# power_distribution.net
KiCad netlist of a schematic drawn in EAGLE
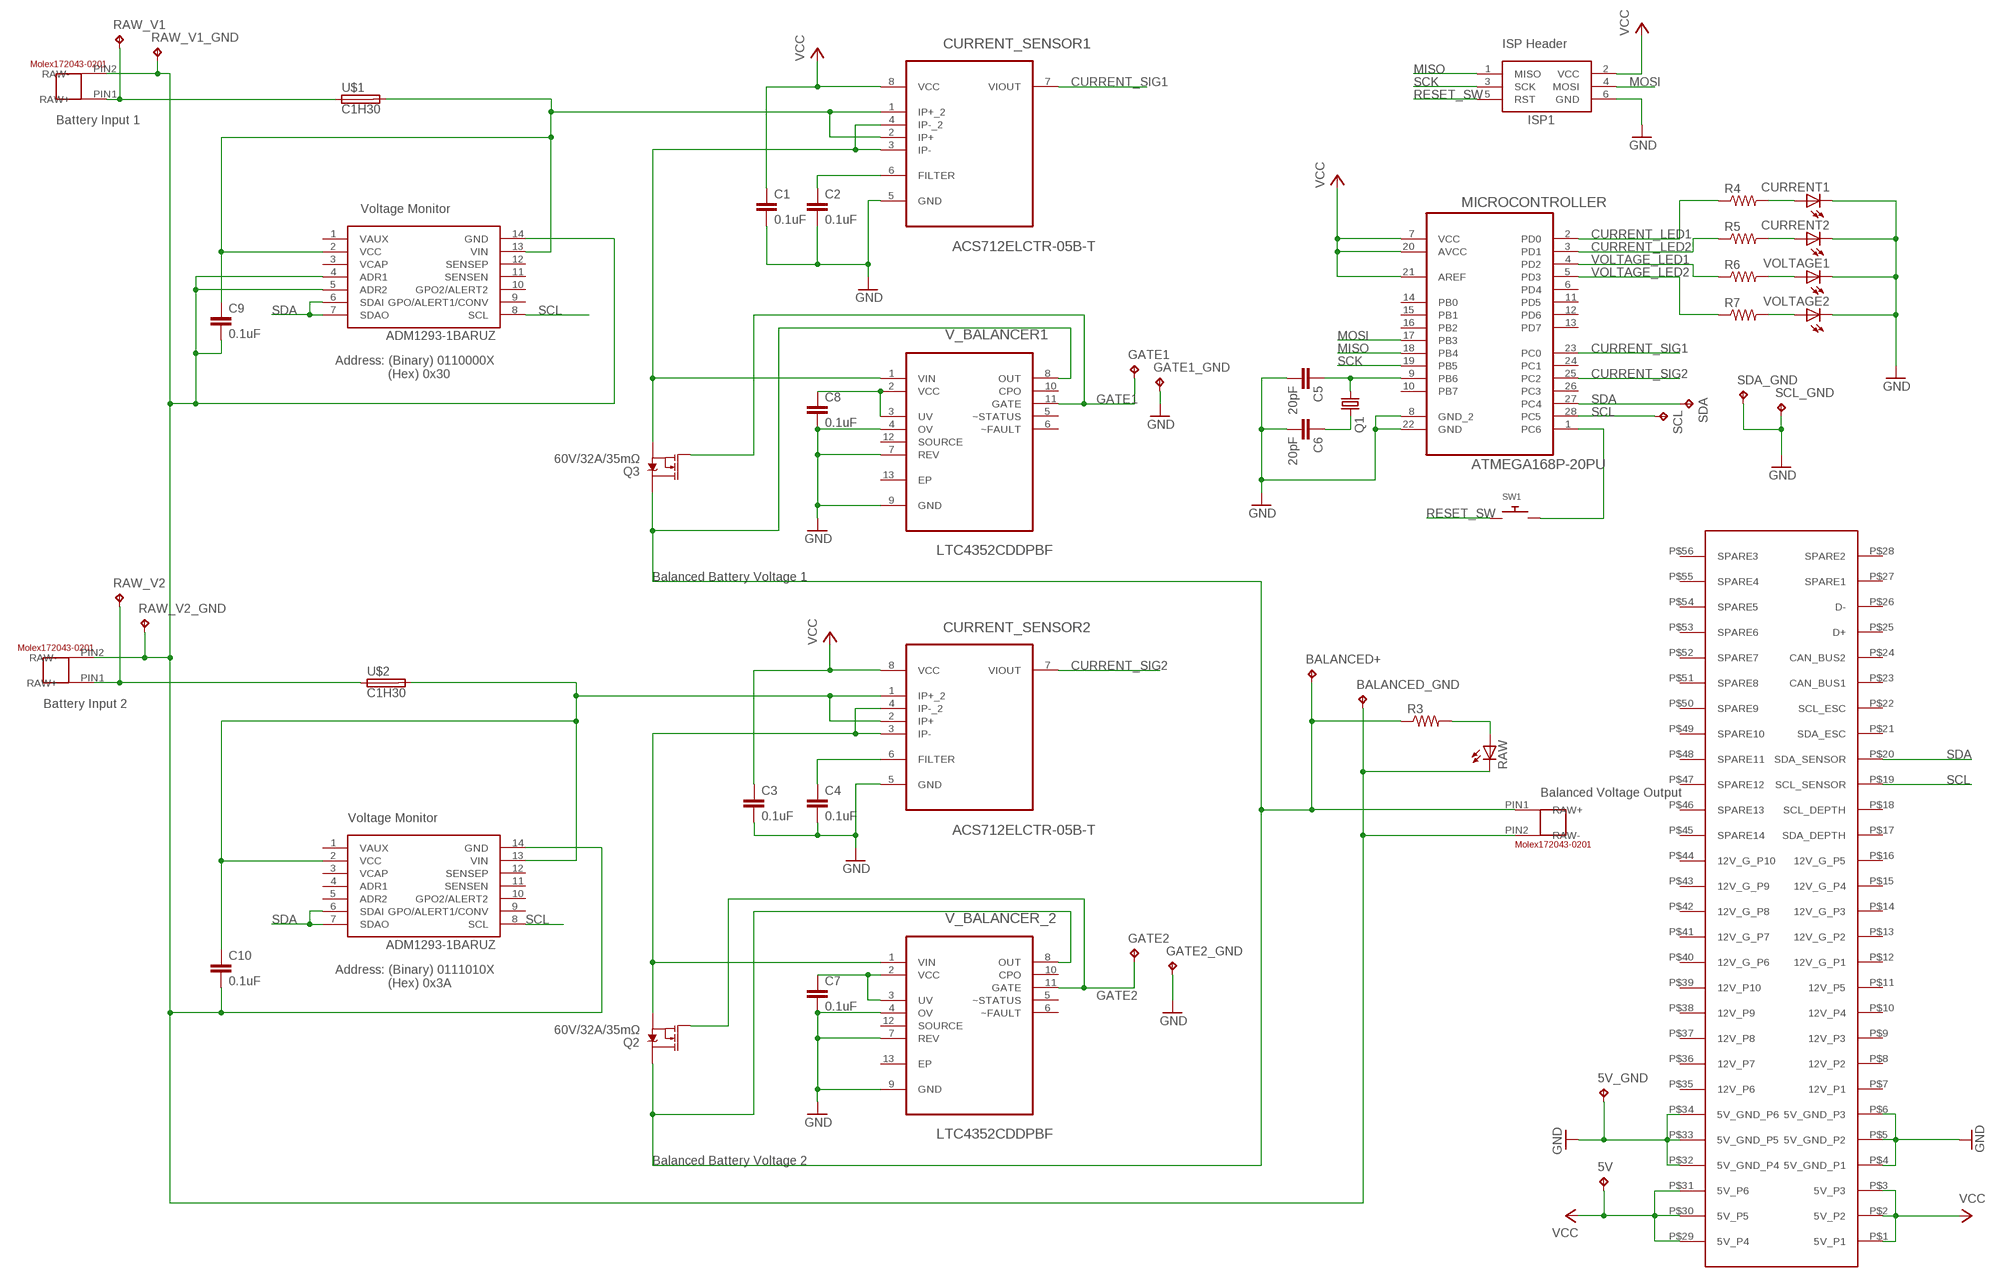
[diagram p0: schematic, sheet 1]

(export (version "E")
  (design (tool "Eeschema 10.0.6"))
  (components
    (comp (ref "5V")
      (value "TPPAD1-13")
      (footprint "eagle-import:P1-13")
      (libsource (lib "eagle-import") (part "TPPAD1-13"))
    )
    (comp (ref "5V_GND")
      (value "TPPAD1-13")
      (footprint "eagle-import:P1-13")
      (libsource (lib "eagle-import") (part "TPPAD1-13"))
    )
    (comp (ref "BALANCED+")
      (value "TPPAD1-13")
      (footprint "eagle-import:P1-13")
      (libsource (lib "eagle-import") (part "TPPAD1-13"))
    )
    (comp (ref "BALANCED_GND")
      (value "TPPAD1-13")
      (footprint "eagle-import:P1-13")
      (libsource (lib "eagle-import") (part "TPPAD1-13"))
    )
    (comp (ref "C1")
      (value "0.1uF")
      (footprint "eagle-import:CAP-PTH-SMALL-KIT")
      (libsource (lib "eagle-import") (part "0.1UF-KIT-EZ-50V-20%"))
    )
    (comp (ref "C2")
      (value "0.1uF")
      (footprint "eagle-import:CAP-PTH-SMALL-KIT")
      (libsource (lib "eagle-import") (part "0.1UF-KIT-EZ-50V-20%"))
    )
    (comp (ref "C3")
      (value "0.1uF")
      (footprint "eagle-import:CAP-PTH-SMALL-KIT")
      (libsource (lib "eagle-import") (part "0.1UF-KIT-EZ-50V-20%"))
    )
    (comp (ref "C4")
      (value "0.1uF")
      (footprint "eagle-import:CAP-PTH-SMALL-KIT")
      (libsource (lib "eagle-import") (part "0.1UF-KIT-EZ-50V-20%"))
    )
    (comp (ref "C5")
      (value "20pF")
      (footprint "eagle-import:CAP-PTH-SMALL-KIT")
      (libsource (lib "eagle-import") (part "0.1UF-KIT-EZ-50V-20%"))
    )
    (comp (ref "C6")
      (value "20pF")
      (footprint "eagle-import:CAP-PTH-SMALL-KIT")
      (libsource (lib "eagle-import") (part "0.1UF-KIT-EZ-50V-20%"))
    )
    (comp (ref "C7")
      (value "0.1uF")
      (footprint "eagle-import:CAP-PTH-SMALL-KIT")
      (libsource (lib "eagle-import") (part "0.1UF-KIT-EZ-50V-20%"))
    )
    (comp (ref "C8")
      (value "0.1uF")
      (footprint "eagle-import:CAP-PTH-SMALL-KIT")
      (libsource (lib "eagle-import") (part "0.1UF-KIT-EZ-50V-20%"))
    )
    (comp (ref "C9")
      (value "0.1uF")
      (footprint "eagle-import:CAP-PTH-SMALL-KIT")
      (libsource (lib "eagle-import") (part "0.1UF-KIT-EZ-50V-20%"))
    )
    (comp (ref "C10")
      (value "0.1uF")
      (footprint "eagle-import:CAP-PTH-SMALL-KIT")
      (libsource (lib "eagle-import") (part "0.1UF-KIT-EZ-50V-20%"))
    )
    (comp (ref "CURRENT1")
      (value "LED3MM")
      (footprint "eagle-import:LED3MM")
      (libsource (lib "eagle-import") (part "LED3MM"))
    )
    (comp (ref "CURRENT2")
      (value "LED3MM")
      (footprint "eagle-import:LED3MM")
      (libsource (lib "eagle-import") (part "LED3MM"))
    )
    (comp (ref "CURRENT_SENSOR1")
      (value "ACS712ELCTR-05B-T")
      (footprint "eagle-import:SOIC127P600X175-8N")
      (libsource (lib "eagle-import") (part "ACS712ELCTR-05B-T"))
    )
    (comp (ref "CURRENT_SENSOR2")
      (value "ACS712ELCTR-05B-T")
      (footprint "eagle-import:SOIC127P600X175-8N")
      (libsource (lib "eagle-import") (part "ACS712ELCTR-05B-T"))
    )
    (comp (ref "GATE1")
      (value "TPPAD1-13")
      (footprint "eagle-import:P1-13")
      (libsource (lib "eagle-import") (part "TPPAD1-13"))
    )
    (comp (ref "GATE1_GND")
      (value "TPPAD1-13")
      (footprint "eagle-import:P1-13")
      (libsource (lib "eagle-import") (part "TPPAD1-13"))
    )
    (comp (ref "GATE2")
      (value "TPPAD1-13")
      (footprint "eagle-import:P1-13")
      (libsource (lib "eagle-import") (part "TPPAD1-13"))
    )
    (comp (ref "GATE2_GND")
      (value "TPPAD1-13")
      (footprint "eagle-import:P1-13")
      (libsource (lib "eagle-import") (part "TPPAD1-13"))
    )
    (comp (ref "INPUT1")
      (value "MOLEX172043-0201")
      (footprint "eagle-import:MOLEX172043-0201")
      (libsource (lib "eagle-import") (part "MOLEX172043-0201"))
    )
    (comp (ref "INPUT2")
      (value "MOLEX172043-0201")
      (footprint "eagle-import:MOLEX172043-0201")
      (libsource (lib "eagle-import") (part "MOLEX172043-0201"))
    )
    (comp (ref "ISP1")
      (value "AVRISP-6")
      (footprint "eagle-import:AVRISP")
      (libsource (lib "eagle-import") (part "AVRISP-6"))
    )
    (comp (ref "MICROCONTROLLER")
      (value "ATMEGA168P-20PU")
      (footprint "eagle-import:DIP254P762X457-28")
      (libsource (lib "eagle-import") (part "ATMEGA168P-20PU"))
    )
    (comp (ref "OUTPUT")
      (value "MOLEX172043-0201")
      (footprint "eagle-import:MOLEX172043-0201")
      (libsource (lib "eagle-import") (part "MOLEX172043-0201"))
    )
    (comp (ref "Q1")
      (value "CRYSTALHC49U-V")
      (footprint "eagle-import:HC49U-V")
      (libsource (lib "eagle-import") (part "CRYSTALHC49U-V"))
    )
    (comp (ref "Q2")
      (value "60V/32A/35mΩ")
      (footprint "eagle-import:TO220V")
      (libsource (lib "eagle-import") (part "MOSFET-NCH-FQP30N06L"))
    )
    (comp (ref "Q3")
      (value "60V/32A/35mΩ")
      (footprint "eagle-import:TO220V")
      (libsource (lib "eagle-import") (part "MOSFET-NCH-FQP30N06L"))
    )
    (comp (ref "R3")
      (value "R-US_0207/12")
      (footprint "eagle-import:0207_12")
      (libsource (lib "eagle-import") (part "R-US_0207/12"))
    )
    (comp (ref "R4")
      (value "R-US_0207/12")
      (footprint "eagle-import:0207_12")
      (libsource (lib "eagle-import") (part "R-US_0207/12"))
    )
    (comp (ref "R5")
      (value "R-US_0207/12")
      (footprint "eagle-import:0207_12")
      (libsource (lib "eagle-import") (part "R-US_0207/12"))
    )
    (comp (ref "R6")
      (value "R-US_0207/12")
      (footprint "eagle-import:0207_12")
      (libsource (lib "eagle-import") (part "R-US_0207/12"))
    )
    (comp (ref "R7")
      (value "R-US_0207/12")
      (footprint "eagle-import:0207_12")
      (libsource (lib "eagle-import") (part "R-US_0207/12"))
    )
    (comp (ref "RAW")
      (value "LED3MM")
      (footprint "eagle-import:LED3MM")
      (libsource (lib "eagle-import") (part "LED3MM"))
    )
    (comp (ref "RAW_V1")
      (value "TPPAD1-13")
      (footprint "eagle-import:P1-13")
      (libsource (lib "eagle-import") (part "TPPAD1-13"))
    )
    (comp (ref "RAW_V1_GND")
      (value "TPPAD1-13")
      (footprint "eagle-import:P1-13")
      (libsource (lib "eagle-import") (part "TPPAD1-13"))
    )
    (comp (ref "RAW_V2")
      (value "TPPAD1-13")
      (footprint "eagle-import:P1-13")
      (libsource (lib "eagle-import") (part "TPPAD1-13"))
    )
    (comp (ref "RAW_V2_GND")
      (value "TPPAD1-13")
      (footprint "eagle-import:P1-13")
      (libsource (lib "eagle-import") (part "TPPAD1-13"))
    )
    (comp (ref "SCL")
      (value "TPPAD1-13")
      (footprint "eagle-import:P1-13")
      (libsource (lib "eagle-import") (part "TPPAD1-13"))
    )
    (comp (ref "SCL_GND")
      (value "TPPAD1-13")
      (footprint "eagle-import:P1-13")
      (libsource (lib "eagle-import") (part "TPPAD1-13"))
    )
    (comp (ref "SDA")
      (value "TPPAD1-13")
      (footprint "eagle-import:P1-13")
      (libsource (lib "eagle-import") (part "TPPAD1-13"))
    )
    (comp (ref "SDA_GND")
      (value "TPPAD1-13")
      (footprint "eagle-import:P1-13")
      (libsource (lib "eagle-import") (part "TPPAD1-13"))
    )
    (comp (ref "SW1")
      (value "SWITCH_PUSHBUTTONEVQ-PE")
      (footprint "eagle-import:TACT_PANA-EVQ")
      (libsource (lib "eagle-import") (part "SWITCH_PUSHBUTTONEVQ-PE"))
    )
    (comp (ref "U$1")
      (value "C1H30")
      (footprint "eagle-import:C1H30")
      (libsource (lib "eagle-import") (part "C1H30"))
    )
    (comp (ref "U$2")
      (value "C1H30")
      (footprint "eagle-import:C1H30")
      (libsource (lib "eagle-import") (part "C1H30"))
    )
    (comp (ref "U$3")
      (value "1-530844-7")
      (footprint "eagle-import:1-530844-7")
      (libsource (lib "eagle-import") (part "1-530844-7"))
    )
    (comp (ref "U$4")
      (value "ADM1293")
      (footprint "eagle-import:SOP65P640X120-14N")
      (libsource (lib "eagle-import") (part "ADM1293"))
    )
    (comp (ref "U$5")
      (value "ADM1293")
      (footprint "eagle-import:SOP65P640X120-14N")
      (libsource (lib "eagle-import") (part "ADM1293"))
    )
    (comp (ref "VOLTAGE1")
      (value "LED3MM")
      (footprint "eagle-import:LED3MM")
      (libsource (lib "eagle-import") (part "LED3MM"))
    )
    (comp (ref "VOLTAGE2")
      (value "LED3MM")
      (footprint "eagle-import:LED3MM")
      (libsource (lib "eagle-import") (part "LED3MM"))
    )
    (comp (ref "V_BALANCER1")
      (value "LTC4352CDDPBF")
      (footprint "eagle-import:DFN300X300X80-13N")
      (fields (field (name "MPN") "LTC4352CDD#PBF"))
      (libsource (lib "eagle-import") (part "LTC4352CDDPBF"))
    )
    (comp (ref "V_BALANCER_2")
      (value "LTC4352CDDPBF")
      (footprint "eagle-import:DFN300X300X80-13N")
      (fields (field (name "MPN") "LTC4352CDD#PBF"))
      (libsource (lib "eagle-import") (part "LTC4352CDDPBF"))
    )
  )
  (nets
    (net (code "1") (name "/CURRENT_LED1") (class "Default")
      (node (ref "MICROCONTROLLER") (pin "2") (pinfunction "PD0_2") (pintype "bidirectional"))
      (node (ref "R4") (pin "1") (pinfunction "1_1") (pintype "passive"))
    )
    (net (code "2") (name "/CURRENT_LED2") (class "Default")
      (node (ref "MICROCONTROLLER") (pin "3") (pinfunction "PD1_3") (pintype "bidirectional"))
      (node (ref "R5") (pin "1") (pinfunction "1_1") (pintype "passive"))
    )
    (net (code "3") (name "/CURRENT_SIG1") (class "Default")
      (node (ref "CURRENT_SENSOR1") (pin "7") (pinfunction "VIOUT_7") (pintype "output"))
      (node (ref "MICROCONTROLLER") (pin "23") (pinfunction "PC0_23") (pintype "bidirectional"))
    )
    (net (code "4") (name "/CURRENT_SIG2") (class "Default")
      (node (ref "CURRENT_SENSOR2") (pin "7") (pinfunction "VIOUT_7") (pintype "output"))
      (node (ref "MICROCONTROLLER") (pin "25") (pinfunction "PC2_25") (pintype "bidirectional"))
    )
    (net (code "5") (name "/GATE1") (class "Default")
      (node (ref "GATE1") (pin "TP") (pinfunction "TP_TP") (pintype "input"))
      (node (ref "Q3") (pin "1") (pinfunction "G_1") (pintype "bidirectional"))
      (node (ref "V_BALANCER1") (pin "11") (pinfunction "GATE_11") (pintype "output"))
    )
    (net (code "6") (name "/GATE2") (class "Default")
      (node (ref "GATE2") (pin "TP") (pinfunction "TP_TP") (pintype "input"))
      (node (ref "Q2") (pin "1") (pinfunction "G_1") (pintype "bidirectional"))
      (node (ref "V_BALANCER_2") (pin "11") (pinfunction "GATE_11") (pintype "output"))
    )
    (net (code "7") (name "/MISO") (class "Default")
      (node (ref "ISP1") (pin "1") (pinfunction "MISO_1") (pintype "input"))
      (node (ref "MICROCONTROLLER") (pin "18") (pinfunction "PB4_18") (pintype "bidirectional"))
    )
    (net (code "8") (name "/MOSI") (class "Default")
      (node (ref "ISP1") (pin "4") (pinfunction "MOSI_4") (pintype "output"))
      (node (ref "MICROCONTROLLER") (pin "17") (pinfunction "PB3_17") (pintype "bidirectional"))
    )
    (net (code "9") (name "/RESET_SW") (class "Default")
      (node (ref "ISP1") (pin "5") (pinfunction "RST_5") (pintype "output"))
      (node (ref "SW1") (pin "P$1") (pinfunction "P$1_P$1") (pintype "passive"))
    )
    (net (code "10") (name "/SCK") (class "Default")
      (node (ref "ISP1") (pin "3") (pinfunction "SCK_3") (pintype "output"))
      (node (ref "MICROCONTROLLER") (pin "19") (pinfunction "PB5_19") (pintype "bidirectional"))
    )
    (net (code "11") (name "/SCL") (class "Default")
      (node (ref "MICROCONTROLLER") (pin "28") (pinfunction "PC5_28") (pintype "bidirectional"))
      (node (ref "SCL") (pin "TP") (pinfunction "TP_TP") (pintype "input"))
      (node (ref "U$3") (pin "P$19") (pinfunction "SCL_SENSOR_P$19") (pintype "bidirectional"))
      (node (ref "U$4") (pin "8") (pinfunction "SCL_8") (pintype "bidirectional"))
      (node (ref "U$5") (pin "8") (pinfunction "SCL_8") (pintype "bidirectional"))
    )
    (net (code "12") (name "/SDA") (class "Default")
      (node (ref "MICROCONTROLLER") (pin "27") (pinfunction "PC4_27") (pintype "bidirectional"))
      (node (ref "SDA") (pin "TP") (pinfunction "TP_TP") (pintype "input"))
      (node (ref "U$3") (pin "P$20") (pinfunction "SDA_SENSOR_P$20") (pintype "bidirectional"))
      (node (ref "U$4") (pin "6") (pinfunction "SDAI_6") (pintype "bidirectional"))
      (node (ref "U$4") (pin "7") (pinfunction "SDAO_7") (pintype "bidirectional"))
      (node (ref "U$5") (pin "6") (pinfunction "SDAI_6") (pintype "bidirectional"))
      (node (ref "U$5") (pin "7") (pinfunction "SDAO_7") (pintype "bidirectional"))
    )
    (net (code "13") (name "/VOLTAGE_LED1") (class "Default")
      (node (ref "MICROCONTROLLER") (pin "4") (pinfunction "PD2_4") (pintype "bidirectional"))
      (node (ref "R6") (pin "1") (pinfunction "1_1") (pintype "passive"))
    )
    (net (code "14") (name "/VOLTAGE_LED2") (class "Default")
      (node (ref "MICROCONTROLLER") (pin "5") (pinfunction "PD3_5") (pintype "bidirectional"))
      (node (ref "R7") (pin "1") (pinfunction "1_1") (pintype "passive"))
    )
    (net (code "15") (name "GND") (class "Default")
      (node (ref "5V_GND") (pin "TP") (pinfunction "TP_TP") (pintype "input"))
      (node (ref "C1") (pin "2") (pinfunction "2_2") (pintype "passive"))
      (node (ref "C2") (pin "2") (pinfunction "2_2") (pintype "passive"))
      (node (ref "C3") (pin "2") (pinfunction "2_2") (pintype "passive"))
      (node (ref "C4") (pin "2") (pinfunction "2_2") (pintype "passive"))
      (node (ref "C5") (pin "2") (pinfunction "2_2") (pintype "passive"))
      (node (ref "C6") (pin "2") (pinfunction "2_2") (pintype "passive"))
      (node (ref "C7") (pin "2") (pinfunction "2_2") (pintype "passive"))
      (node (ref "C8") (pin "2") (pinfunction "2_2") (pintype "passive"))
      (node (ref "CURRENT1") (pin "K") (pinfunction "C_K") (pintype "passive"))
      (node (ref "CURRENT2") (pin "K") (pinfunction "C_K") (pintype "passive"))
      (node (ref "CURRENT_SENSOR1") (pin "5") (pinfunction "GND_5") (pintype "passive"))
      (node (ref "CURRENT_SENSOR2") (pin "5") (pinfunction "GND_5") (pintype "passive"))
      (node (ref "GATE1_GND") (pin "TP") (pinfunction "TP_TP") (pintype "input"))
      (node (ref "GATE2_GND") (pin "TP") (pinfunction "TP_TP") (pintype "input"))
      (node (ref "ISP1") (pin "6") (pinfunction "GND_6") (pintype "power_in"))
      (node (ref "MICROCONTROLLER") (pin "22") (pinfunction "GND_22") (pintype "passive"))
      (node (ref "MICROCONTROLLER") (pin "8") (pinfunction "GND_2_8") (pintype "passive"))
      (node (ref "SCL_GND") (pin "TP") (pinfunction "TP_TP") (pintype "input"))
      (node (ref "SDA_GND") (pin "TP") (pinfunction "TP_TP") (pintype "input"))
      (node (ref "U$3") (pin "P$32") (pinfunction "5V_GND_P4_P$32") (pintype "bidirectional"))
      (node (ref "U$3") (pin "P$33") (pinfunction "5V_GND_P5_P$33") (pintype "bidirectional"))
      (node (ref "U$3") (pin "P$34") (pinfunction "5V_GND_P6_P$34") (pintype "bidirectional"))
      (node (ref "U$3") (pin "P$4") (pinfunction "5V_GND_P1_P$4") (pintype "bidirectional"))
      (node (ref "U$3") (pin "P$5") (pinfunction "5V_GND_P2_P$5") (pintype "bidirectional"))
      (node (ref "U$3") (pin "P$6") (pinfunction "5V_GND_P3_P$6") (pintype "bidirectional"))
      (node (ref "VOLTAGE1") (pin "K") (pinfunction "C_K") (pintype "passive"))
      (node (ref "VOLTAGE2") (pin "K") (pinfunction "C_K") (pintype "passive"))
      (node (ref "V_BALANCER1") (pin "4") (pinfunction "OV_4") (pintype "input"))
      (node (ref "V_BALANCER1") (pin "7") (pinfunction "REV_7") (pintype "input"))
      (node (ref "V_BALANCER1") (pin "9") (pinfunction "GND_9") (pintype "passive"))
      (node (ref "V_BALANCER_2") (pin "4") (pinfunction "OV_4") (pintype "input"))
      (node (ref "V_BALANCER_2") (pin "7") (pinfunction "REV_7") (pintype "input"))
      (node (ref "V_BALANCER_2") (pin "9") (pinfunction "GND_9") (pintype "passive"))
    )
    (net (code "16") (name "Net-(C6-Pad1)") (class "Default")
      (node (ref "C6") (pin "1") (pinfunction "1_1") (pintype "passive"))
      (node (ref "Q1") (pin "2") (pinfunction "2_2") (pintype "passive"))
    )
    (net (code "17") (name "Net-(CURRENT1-PadA)") (class "Default")
      (node (ref "CURRENT1") (pin "A") (pinfunction "A_A") (pintype "passive"))
      (node (ref "R4") (pin "2") (pinfunction "2_2") (pintype "passive"))
    )
    (net (code "18") (name "Net-(CURRENT2-PadA)") (class "Default")
      (node (ref "CURRENT2") (pin "A") (pinfunction "A_A") (pintype "passive"))
      (node (ref "R5") (pin "2") (pinfunction "2_2") (pintype "passive"))
    )
    (net (code "19") (name "Net-(CURRENT_SENSOR1-FILTER)") (class "Default")
      (node (ref "C2") (pin "1") (pinfunction "1_1") (pintype "passive"))
      (node (ref "CURRENT_SENSOR1") (pin "6") (pinfunction "FILTER_6") (pintype "input"))
    )
    (net (code "20") (name "Net-(CURRENT_SENSOR1-IP+)") (class "Default")
      (node (ref "C9") (pin "1") (pinfunction "1_1") (pintype "passive"))
      (node (ref "CURRENT_SENSOR1") (pin "1") (pinfunction "IP+_2_1") (pintype "input"))
      (node (ref "CURRENT_SENSOR1") (pin "2") (pinfunction "IP+_2") (pintype "input"))
      (node (ref "U$1") (pin "P$2") (pinfunction "2_P$2") (pintype "passive"))
      (node (ref "U$4") (pin "13") (pinfunction "VIN_13") (pintype "bidirectional"))
      (node (ref "U$4") (pin "2") (pinfunction "VCC_2") (pintype "bidirectional"))
    )
    (net (code "21") (name "Net-(CURRENT_SENSOR1-IP-)") (class "Default")
      (node (ref "CURRENT_SENSOR1") (pin "3") (pinfunction "IP-_3") (pintype "input"))
      (node (ref "CURRENT_SENSOR1") (pin "4") (pinfunction "IP-_2_4") (pintype "input"))
      (node (ref "Q3") (pin "3") (pinfunction "S_3") (pintype "bidirectional"))
      (node (ref "V_BALANCER1") (pin "1") (pinfunction "VIN_1") (pintype "power_in"))
    )
    (net (code "22") (name "Net-(CURRENT_SENSOR2-FILTER)") (class "Default")
      (node (ref "C4") (pin "1") (pinfunction "1_1") (pintype "passive"))
      (node (ref "CURRENT_SENSOR2") (pin "6") (pinfunction "FILTER_6") (pintype "input"))
    )
    (net (code "23") (name "Net-(CURRENT_SENSOR2-IP+)") (class "Default")
      (node (ref "C10") (pin "1") (pinfunction "1_1") (pintype "passive"))
      (node (ref "CURRENT_SENSOR2") (pin "1") (pinfunction "IP+_2_1") (pintype "input"))
      (node (ref "CURRENT_SENSOR2") (pin "2") (pinfunction "IP+_2") (pintype "input"))
      (node (ref "U$2") (pin "P$2") (pinfunction "2_P$2") (pintype "passive"))
      (node (ref "U$5") (pin "13") (pinfunction "VIN_13") (pintype "bidirectional"))
      (node (ref "U$5") (pin "2") (pinfunction "VCC_2") (pintype "bidirectional"))
    )
    (net (code "24") (name "Net-(CURRENT_SENSOR2-IP-)") (class "Default")
      (node (ref "CURRENT_SENSOR2") (pin "3") (pinfunction "IP-_3") (pintype "input"))
      (node (ref "CURRENT_SENSOR2") (pin "4") (pinfunction "IP-_2_4") (pintype "input"))
      (node (ref "Q2") (pin "3") (pinfunction "S_3") (pintype "bidirectional"))
      (node (ref "V_BALANCER_2") (pin "1") (pinfunction "VIN_1") (pintype "power_in"))
    )
    (net (code "25") (name "Net-(INPUT1-RAW+)") (class "Default")
      (node (ref "INPUT1") (pin "PIN1") (pinfunction "RAW+_PIN1") (pintype "bidirectional"))
      (node (ref "RAW_V1") (pin "TP") (pinfunction "TP_TP") (pintype "input"))
      (node (ref "U$1") (pin "P$1") (pinfunction "1_P$1") (pintype "passive"))
    )
    (net (code "26") (name "Net-(INPUT1-RAW-)") (class "Default")
      (node (ref "BALANCED_GND") (pin "TP") (pinfunction "TP_TP") (pintype "input"))
      (node (ref "C10") (pin "2") (pinfunction "2_2") (pintype "passive"))
      (node (ref "C9") (pin "2") (pinfunction "2_2") (pintype "passive"))
      (node (ref "INPUT1") (pin "PIN2") (pinfunction "RAW-_PIN2") (pintype "bidirectional"))
      (node (ref "INPUT2") (pin "PIN2") (pinfunction "RAW-_PIN2") (pintype "bidirectional"))
      (node (ref "OUTPUT") (pin "PIN2") (pinfunction "RAW-_PIN2") (pintype "bidirectional"))
      (node (ref "RAW") (pin "K") (pinfunction "C_K") (pintype "passive"))
      (node (ref "RAW_V1_GND") (pin "TP") (pinfunction "TP_TP") (pintype "input"))
      (node (ref "RAW_V2_GND") (pin "TP") (pinfunction "TP_TP") (pintype "input"))
      (node (ref "U$4") (pin "14") (pinfunction "GND_14") (pintype "bidirectional"))
      (node (ref "U$4") (pin "4") (pinfunction "ADR1_4") (pintype "bidirectional"))
      (node (ref "U$4") (pin "5") (pinfunction "ADR2_5") (pintype "bidirectional"))
      (node (ref "U$5") (pin "14") (pinfunction "GND_14") (pintype "bidirectional"))
    )
    (net (code "27") (name "Net-(INPUT2-RAW+)") (class "Default")
      (node (ref "INPUT2") (pin "PIN1") (pinfunction "RAW+_PIN1") (pintype "bidirectional"))
      (node (ref "RAW_V2") (pin "TP") (pinfunction "TP_TP") (pintype "input"))
      (node (ref "U$2") (pin "P$1") (pinfunction "1_P$1") (pintype "passive"))
    )
    (net (code "28") (name "Net-(MICROCONTROLLER-PB6)") (class "Default")
      (node (ref "C5") (pin "1") (pinfunction "1_1") (pintype "passive"))
      (node (ref "MICROCONTROLLER") (pin "9") (pinfunction "PB6_9") (pintype "bidirectional"))
      (node (ref "Q1") (pin "1") (pinfunction "1_1") (pintype "passive"))
    )
    (net (code "29") (name "Net-(MICROCONTROLLER-PC6)") (class "Default")
      (node (ref "MICROCONTROLLER") (pin "1") (pinfunction "PC6_1") (pintype "bidirectional"))
      (node (ref "SW1") (pin "P$2") (pinfunction "P$2_P$2") (pintype "passive"))
    )
    (net (code "30") (name "Net-(OUTPUT-RAW+)") (class "Default")
      (node (ref "BALANCED+") (pin "TP") (pinfunction "TP_TP") (pintype "input"))
      (node (ref "OUTPUT") (pin "PIN1") (pinfunction "RAW+_PIN1") (pintype "bidirectional"))
      (node (ref "Q2") (pin "2") (pinfunction "D_2") (pintype "bidirectional"))
      (node (ref "Q3") (pin "2") (pinfunction "D_2") (pintype "bidirectional"))
      (node (ref "R3") (pin "1") (pinfunction "1_1") (pintype "passive"))
      (node (ref "V_BALANCER1") (pin "8") (pinfunction "OUT_8") (pintype "output"))
      (node (ref "V_BALANCER_2") (pin "8") (pinfunction "OUT_8") (pintype "output"))
    )
    (net (code "31") (name "Net-(R3-Pad2)") (class "Default")
      (node (ref "R3") (pin "2") (pinfunction "2_2") (pintype "passive"))
      (node (ref "RAW") (pin "A") (pinfunction "A_A") (pintype "passive"))
    )
    (net (code "32") (name "Net-(R6-Pad2)") (class "Default")
      (node (ref "R6") (pin "2") (pinfunction "2_2") (pintype "passive"))
      (node (ref "VOLTAGE1") (pin "A") (pinfunction "A_A") (pintype "passive"))
    )
    (net (code "33") (name "Net-(R7-Pad2)") (class "Default")
      (node (ref "R7") (pin "2") (pinfunction "2_2") (pintype "passive"))
      (node (ref "VOLTAGE2") (pin "A") (pinfunction "A_A") (pintype "passive"))
    )
    (net (code "34") (name "Net-(V_BALANCER1-UV)") (class "Default")
      (node (ref "C8") (pin "1") (pinfunction "1_1") (pintype "passive"))
      (node (ref "V_BALANCER1") (pin "2") (pinfunction "VCC_2") (pintype "power_in"))
      (node (ref "V_BALANCER1") (pin "3") (pinfunction "UV_3") (pintype "input"))
    )
    (net (code "35") (name "Net-(V_BALANCER_2-UV)") (class "Default")
      (node (ref "C7") (pin "1") (pinfunction "1_1") (pintype "passive"))
      (node (ref "V_BALANCER_2") (pin "2") (pinfunction "VCC_2") (pintype "power_in"))
      (node (ref "V_BALANCER_2") (pin "3") (pinfunction "UV_3") (pintype "input"))
    )
    (net (code "36") (name "VCC") (class "Default")
      (node (ref "5V") (pin "TP") (pinfunction "TP_TP") (pintype "input"))
      (node (ref "C1") (pin "1") (pinfunction "1_1") (pintype "passive"))
      (node (ref "C3") (pin "1") (pinfunction "1_1") (pintype "passive"))
      (node (ref "CURRENT_SENSOR1") (pin "8") (pinfunction "VCC_8") (pintype "power_in"))
      (node (ref "CURRENT_SENSOR2") (pin "8") (pinfunction "VCC_8") (pintype "power_in"))
      (node (ref "ISP1") (pin "2") (pinfunction "VCC_2") (pintype "power_in"))
      (node (ref "MICROCONTROLLER") (pin "20") (pinfunction "AVCC_20") (pintype "power_in"))
      (node (ref "MICROCONTROLLER") (pin "21") (pinfunction "AREF_21") (pintype "input"))
      (node (ref "MICROCONTROLLER") (pin "7") (pinfunction "VCC_7") (pintype "power_in"))
      (node (ref "U$3") (pin "P$1") (pinfunction "5V_P1_P$1") (pintype "bidirectional"))
      (node (ref "U$3") (pin "P$2") (pinfunction "5V_P2_P$2") (pintype "bidirectional"))
      (node (ref "U$3") (pin "P$29") (pinfunction "5V_P4_P$29") (pintype "bidirectional"))
      (node (ref "U$3") (pin "P$3") (pinfunction "5V_P3_P$3") (pintype "bidirectional"))
      (node (ref "U$3") (pin "P$30") (pinfunction "5V_P5_P$30") (pintype "bidirectional"))
      (node (ref "U$3") (pin "P$31") (pinfunction "5V_P6_P$31") (pintype "bidirectional"))
    )
    (net (code "37") (name "unconnected-(MICROCONTROLLER-PB0-Pad14)") (class "Default")
      (node (ref "MICROCONTROLLER") (pin "14") (pinfunction "PB0_14") (pintype "bidirectional"))
    )
    (net (code "38") (name "unconnected-(MICROCONTROLLER-PB1-Pad15)") (class "Default")
      (node (ref "MICROCONTROLLER") (pin "15") (pinfunction "PB1_15") (pintype "bidirectional"))
    )
    (net (code "39") (name "unconnected-(MICROCONTROLLER-PB2-Pad16)") (class "Default")
      (node (ref "MICROCONTROLLER") (pin "16") (pinfunction "PB2_16") (pintype "bidirectional"))
    )
    (net (code "40") (name "unconnected-(MICROCONTROLLER-PB7-Pad10)") (class "Default")
      (node (ref "MICROCONTROLLER") (pin "10") (pinfunction "PB7_10") (pintype "bidirectional"))
    )
    (net (code "41") (name "unconnected-(MICROCONTROLLER-PC1-Pad24)") (class "Default")
      (node (ref "MICROCONTROLLER") (pin "24") (pinfunction "PC1_24") (pintype "bidirectional"))
    )
    (net (code "42") (name "unconnected-(MICROCONTROLLER-PC3-Pad26)") (class "Default")
      (node (ref "MICROCONTROLLER") (pin "26") (pinfunction "PC3_26") (pintype "bidirectional"))
    )
    (net (code "43") (name "unconnected-(MICROCONTROLLER-PD4-Pad6)") (class "Default")
      (node (ref "MICROCONTROLLER") (pin "6") (pinfunction "PD4_6") (pintype "bidirectional"))
    )
    (net (code "44") (name "unconnected-(MICROCONTROLLER-PD5-Pad11)") (class "Default")
      (node (ref "MICROCONTROLLER") (pin "11") (pinfunction "PD5_11") (pintype "bidirectional"))
    )
    (net (code "45") (name "unconnected-(MICROCONTROLLER-PD6-Pad12)") (class "Default")
      (node (ref "MICROCONTROLLER") (pin "12") (pinfunction "PD6_12") (pintype "bidirectional"))
    )
    (net (code "46") (name "unconnected-(MICROCONTROLLER-PD7-Pad13)") (class "Default")
      (node (ref "MICROCONTROLLER") (pin "13") (pinfunction "PD7_13") (pintype "bidirectional"))
    )
    (net (code "47") (name "unconnected-(U$3-12V_G_P1-PadP$12)") (class "Default")
      (node (ref "U$3") (pin "P$12") (pinfunction "12V_G_P1_P$12") (pintype "bidirectional"))
    )
    (net (code "48") (name "unconnected-(U$3-12V_G_P2-PadP$13)") (class "Default")
      (node (ref "U$3") (pin "P$13") (pinfunction "12V_G_P2_P$13") (pintype "bidirectional"))
    )
    (net (code "49") (name "unconnected-(U$3-12V_G_P3-PadP$14)") (class "Default")
      (node (ref "U$3") (pin "P$14") (pinfunction "12V_G_P3_P$14") (pintype "bidirectional"))
    )
    (net (code "50") (name "unconnected-(U$3-12V_G_P4-PadP$15)") (class "Default")
      (node (ref "U$3") (pin "P$15") (pinfunction "12V_G_P4_P$15") (pintype "bidirectional"))
    )
    (net (code "51") (name "unconnected-(U$3-12V_G_P5-PadP$16)") (class "Default")
      (node (ref "U$3") (pin "P$16") (pinfunction "12V_G_P5_P$16") (pintype "bidirectional"))
    )
    (net (code "52") (name "unconnected-(U$3-12V_G_P6-PadP$40)") (class "Default")
      (node (ref "U$3") (pin "P$40") (pinfunction "12V_G_P6_P$40") (pintype "bidirectional"))
    )
    (net (code "53") (name "unconnected-(U$3-12V_G_P7-PadP$41)") (class "Default")
      (node (ref "U$3") (pin "P$41") (pinfunction "12V_G_P7_P$41") (pintype "bidirectional"))
    )
    (net (code "54") (name "unconnected-(U$3-12V_G_P8-PadP$42)") (class "Default")
      (node (ref "U$3") (pin "P$42") (pinfunction "12V_G_P8_P$42") (pintype "bidirectional"))
    )
    (net (code "55") (name "unconnected-(U$3-12V_G_P9-PadP$43)") (class "Default")
      (node (ref "U$3") (pin "P$43") (pinfunction "12V_G_P9_P$43") (pintype "bidirectional"))
    )
    (net (code "56") (name "unconnected-(U$3-12V_G_P10-PadP$44)") (class "Default")
      (node (ref "U$3") (pin "P$44") (pinfunction "12V_G_P10_P$44") (pintype "bidirectional"))
    )
    (net (code "57") (name "unconnected-(U$3-12V_P1-PadP$7)") (class "Default")
      (node (ref "U$3") (pin "P$7") (pinfunction "12V_P1_P$7") (pintype "bidirectional"))
    )
    (net (code "58") (name "unconnected-(U$3-12V_P2-PadP$8)") (class "Default")
      (node (ref "U$3") (pin "P$8") (pinfunction "12V_P2_P$8") (pintype "bidirectional"))
    )
    (net (code "59") (name "unconnected-(U$3-12V_P3-PadP$9)") (class "Default")
      (node (ref "U$3") (pin "P$9") (pinfunction "12V_P3_P$9") (pintype "bidirectional"))
    )
    (net (code "60") (name "unconnected-(U$3-12V_P4-PadP$10)") (class "Default")
      (node (ref "U$3") (pin "P$10") (pinfunction "12V_P4_P$10") (pintype "bidirectional"))
    )
    (net (code "61") (name "unconnected-(U$3-12V_P5-PadP$11)") (class "Default")
      (node (ref "U$3") (pin "P$11") (pinfunction "12V_P5_P$11") (pintype "bidirectional"))
    )
    (net (code "62") (name "unconnected-(U$3-12V_P6-PadP$35)") (class "Default")
      (node (ref "U$3") (pin "P$35") (pinfunction "12V_P6_P$35") (pintype "bidirectional"))
    )
    (net (code "63") (name "unconnected-(U$3-12V_P7-PadP$36)") (class "Default")
      (node (ref "U$3") (pin "P$36") (pinfunction "12V_P7_P$36") (pintype "bidirectional"))
    )
    (net (code "64") (name "unconnected-(U$3-12V_P8-PadP$37)") (class "Default")
      (node (ref "U$3") (pin "P$37") (pinfunction "12V_P8_P$37") (pintype "bidirectional"))
    )
    (net (code "65") (name "unconnected-(U$3-12V_P9-PadP$38)") (class "Default")
      (node (ref "U$3") (pin "P$38") (pinfunction "12V_P9_P$38") (pintype "bidirectional"))
    )
    (net (code "66") (name "unconnected-(U$3-12V_P10-PadP$39)") (class "Default")
      (node (ref "U$3") (pin "P$39") (pinfunction "12V_P10_P$39") (pintype "bidirectional"))
    )
    (net (code "67") (name "unconnected-(U$3-CAN_BUS1-PadP$23)") (class "Default")
      (node (ref "U$3") (pin "P$23") (pinfunction "CAN_BUS1_P$23") (pintype "bidirectional"))
    )
    (net (code "68") (name "unconnected-(U$3-CAN_BUS2-PadP$24)") (class "Default")
      (node (ref "U$3") (pin "P$24") (pinfunction "CAN_BUS2_P$24") (pintype "bidirectional"))
    )
    (net (code "69") (name "unconnected-(U$3-D+-PadP$25)") (class "Default")
      (node (ref "U$3") (pin "P$25") (pinfunction "D+_P$25") (pintype "bidirectional"))
    )
    (net (code "70") (name "unconnected-(U$3-D--PadP$26)") (class "Default")
      (node (ref "U$3") (pin "P$26") (pinfunction "D-_P$26") (pintype "bidirectional"))
    )
    (net (code "71") (name "unconnected-(U$3-SCL_DEPTH-PadP$18)") (class "Default")
      (node (ref "U$3") (pin "P$18") (pinfunction "SCL_DEPTH_P$18") (pintype "bidirectional"))
    )
    (net (code "72") (name "unconnected-(U$3-SCL_ESC-PadP$22)") (class "Default")
      (node (ref "U$3") (pin "P$22") (pinfunction "SCL_ESC_P$22") (pintype "bidirectional"))
    )
    (net (code "73") (name "unconnected-(U$3-SDA_DEPTH-PadP$17)") (class "Default")
      (node (ref "U$3") (pin "P$17") (pinfunction "SDA_DEPTH_P$17") (pintype "bidirectional"))
    )
    (net (code "74") (name "unconnected-(U$3-SDA_ESC-PadP$21)") (class "Default")
      (node (ref "U$3") (pin "P$21") (pinfunction "SDA_ESC_P$21") (pintype "bidirectional"))
    )
    (net (code "75") (name "unconnected-(U$3-SPARE1-PadP$27)") (class "Default")
      (node (ref "U$3") (pin "P$27") (pinfunction "SPARE1_P$27") (pintype "bidirectional"))
    )
    (net (code "76") (name "unconnected-(U$3-SPARE2-PadP$28)") (class "Default")
      (node (ref "U$3") (pin "P$28") (pinfunction "SPARE2_P$28") (pintype "bidirectional"))
    )
    (net (code "77") (name "unconnected-(U$3-SPARE3-PadP$56)") (class "Default")
      (node (ref "U$3") (pin "P$56") (pinfunction "SPARE3_P$56") (pintype "bidirectional"))
    )
    (net (code "78") (name "unconnected-(U$3-SPARE4-PadP$55)") (class "Default")
      (node (ref "U$3") (pin "P$55") (pinfunction "SPARE4_P$55") (pintype "bidirectional"))
    )
    (net (code "79") (name "unconnected-(U$3-SPARE5-PadP$54)") (class "Default")
      (node (ref "U$3") (pin "P$54") (pinfunction "SPARE5_P$54") (pintype "bidirectional"))
    )
    (net (code "80") (name "unconnected-(U$3-SPARE6-PadP$53)") (class "Default")
      (node (ref "U$3") (pin "P$53") (pinfunction "SPARE6_P$53") (pintype "bidirectional"))
    )
    (net (code "81") (name "unconnected-(U$3-SPARE7-PadP$52)") (class "Default")
      (node (ref "U$3") (pin "P$52") (pinfunction "SPARE7_P$52") (pintype "bidirectional"))
    )
    (net (code "82") (name "unconnected-(U$3-SPARE8-PadP$51)") (class "Default")
      (node (ref "U$3") (pin "P$51") (pinfunction "SPARE8_P$51") (pintype "bidirectional"))
    )
    (net (code "83") (name "unconnected-(U$3-SPARE9-PadP$50)") (class "Default")
      (node (ref "U$3") (pin "P$50") (pinfunction "SPARE9_P$50") (pintype "bidirectional"))
    )
    (net (code "84") (name "unconnected-(U$3-SPARE10-PadP$49)") (class "Default")
      (node (ref "U$3") (pin "P$49") (pinfunction "SPARE10_P$49") (pintype "bidirectional"))
    )
    (net (code "85") (name "unconnected-(U$3-SPARE11-PadP$48)") (class "Default")
      (node (ref "U$3") (pin "P$48") (pinfunction "SPARE11_P$48") (pintype "bidirectional"))
    )
    (net (code "86") (name "unconnected-(U$3-SPARE12-PadP$47)") (class "Default")
      (node (ref "U$3") (pin "P$47") (pinfunction "SPARE12_P$47") (pintype "bidirectional"))
    )
    (net (code "87") (name "unconnected-(U$3-SPARE13-PadP$46)") (class "Default")
      (node (ref "U$3") (pin "P$46") (pinfunction "SPARE13_P$46") (pintype "bidirectional"))
    )
    (net (code "88") (name "unconnected-(U$3-SPARE14-PadP$45)") (class "Default")
      (node (ref "U$3") (pin "P$45") (pinfunction "SPARE14_P$45") (pintype "bidirectional"))
    )
    (net (code "89") (name "unconnected-(U$4-GPO2{slash}ALERT2-Pad10)") (class "Default")
      (node (ref "U$4") (pin "10") (pinfunction "GPO2/ALERT2_10") (pintype "bidirectional"))
    )
    (net (code "90") (name "unconnected-(U$4-GPO{slash}ALERT1{slash}CONV-Pad9)") (class "Default")
      (node (ref "U$4") (pin "9") (pinfunction "GPO/ALERT1/CONV_9") (pintype "bidirectional"))
    )
    (net (code "91") (name "unconnected-(U$4-SENSEN-Pad11)") (class "Default")
      (node (ref "U$4") (pin "11") (pinfunction "SENSEN_11") (pintype "bidirectional"))
    )
    (net (code "92") (name "unconnected-(U$4-SENSEP-Pad12)") (class "Default")
      (node (ref "U$4") (pin "12") (pinfunction "SENSEP_12") (pintype "bidirectional"))
    )
    (net (code "93") (name "unconnected-(U$4-VAUX-Pad1)") (class "Default")
      (node (ref "U$4") (pin "1") (pinfunction "VAUX_1") (pintype "bidirectional"))
    )
    (net (code "94") (name "unconnected-(U$4-VCAP-Pad3)") (class "Default")
      (node (ref "U$4") (pin "3") (pinfunction "VCAP_3") (pintype "bidirectional"))
    )
    (net (code "95") (name "unconnected-(U$5-ADR1-Pad4)") (class "Default")
      (node (ref "U$5") (pin "4") (pinfunction "ADR1_4") (pintype "bidirectional"))
    )
    (net (code "96") (name "unconnected-(U$5-ADR2-Pad5)") (class "Default")
      (node (ref "U$5") (pin "5") (pinfunction "ADR2_5") (pintype "bidirectional"))
    )
    (net (code "97") (name "unconnected-(U$5-GPO2{slash}ALERT2-Pad10)") (class "Default")
      (node (ref "U$5") (pin "10") (pinfunction "GPO2/ALERT2_10") (pintype "bidirectional"))
    )
    (net (code "98") (name "unconnected-(U$5-GPO{slash}ALERT1{slash}CONV-Pad9)") (class "Default")
      (node (ref "U$5") (pin "9") (pinfunction "GPO/ALERT1/CONV_9") (pintype "bidirectional"))
    )
    (net (code "99") (name "unconnected-(U$5-SENSEN-Pad11)") (class "Default")
      (node (ref "U$5") (pin "11") (pinfunction "SENSEN_11") (pintype "bidirectional"))
    )
    (net (code "100") (name "unconnected-(U$5-SENSEP-Pad12)") (class "Default")
      (node (ref "U$5") (pin "12") (pinfunction "SENSEP_12") (pintype "bidirectional"))
    )
    (net (code "101") (name "unconnected-(U$5-VAUX-Pad1)") (class "Default")
      (node (ref "U$5") (pin "1") (pinfunction "VAUX_1") (pintype "bidirectional"))
    )
    (net (code "102") (name "unconnected-(U$5-VCAP-Pad3)") (class "Default")
      (node (ref "U$5") (pin "3") (pinfunction "VCAP_3") (pintype "bidirectional"))
    )
    (net (code "103") (name "unconnected-(V_BALANCER1-CPO-Pad10)") (class "Default")
      (node (ref "V_BALANCER1") (pin "10") (pinfunction "CPO_10") (pintype "output"))
    )
    (net (code "104") (name "unconnected-(V_BALANCER1-EP-Pad13)") (class "Default")
      (node (ref "V_BALANCER1") (pin "13") (pinfunction "EP_13") (pintype "passive"))
    )
    (net (code "105") (name "unconnected-(V_BALANCER1-SOURCE-Pad12)") (class "Default")
      (node (ref "V_BALANCER1") (pin "12") (pinfunction "SOURCE_12") (pintype "input"))
    )
    (net (code "106") (name "unconnected-(V_BALANCER1-~{FAULT}-Pad6)") (class "Default")
      (node (ref "V_BALANCER1") (pin "6") (pinfunction "~{FAULT}_6") (pintype "output"))
    )
    (net (code "107") (name "unconnected-(V_BALANCER1-~{STATUS}-Pad5)") (class "Default")
      (node (ref "V_BALANCER1") (pin "5") (pinfunction "~{STATUS}_5") (pintype "output"))
    )
    (net (code "108") (name "unconnected-(V_BALANCER_2-CPO-Pad10)") (class "Default")
      (node (ref "V_BALANCER_2") (pin "10") (pinfunction "CPO_10") (pintype "output"))
    )
    (net (code "109") (name "unconnected-(V_BALANCER_2-EP-Pad13)") (class "Default")
      (node (ref "V_BALANCER_2") (pin "13") (pinfunction "EP_13") (pintype "passive"))
    )
    (net (code "110") (name "unconnected-(V_BALANCER_2-SOURCE-Pad12)") (class "Default")
      (node (ref "V_BALANCER_2") (pin "12") (pinfunction "SOURCE_12") (pintype "input"))
    )
    (net (code "111") (name "unconnected-(V_BALANCER_2-~{FAULT}-Pad6)") (class "Default")
      (node (ref "V_BALANCER_2") (pin "6") (pinfunction "~{FAULT}_6") (pintype "output"))
    )
    (net (code "112") (name "unconnected-(V_BALANCER_2-~{STATUS}-Pad5)") (class "Default")
      (node (ref "V_BALANCER_2") (pin "5") (pinfunction "~{STATUS}_5") (pintype "output"))
    )
  )
)
